# MainControl.net
KiCad netlist of a schematic drawn in EAGLE
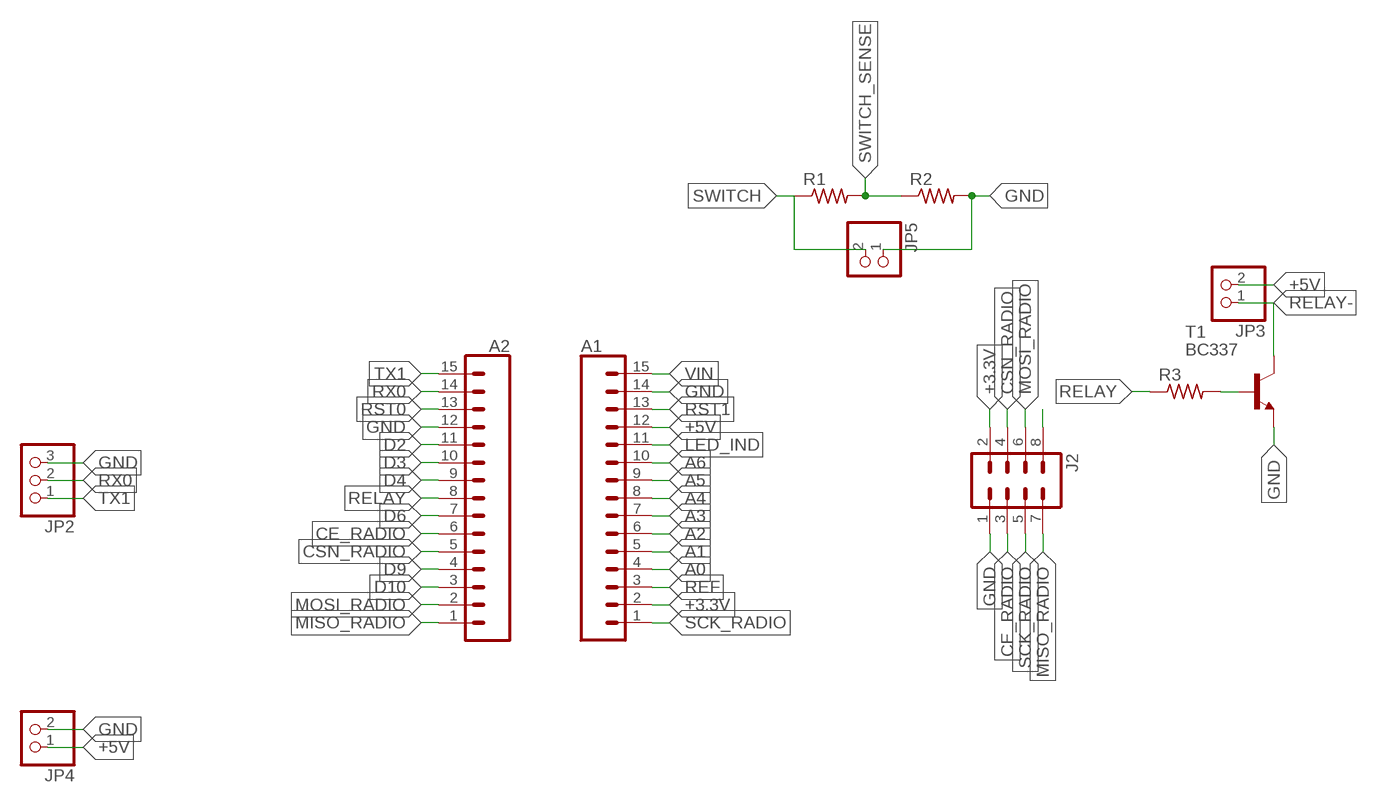
[diagram p0: schematic, sheet 1]

(export (version "E")
  (design (tool "Eeschema 10.0.6"))
  (components
    (comp (ref "A1")
      (value "CONN_15")
      (footprint "eagle-import:1X15")
      (fields (field (name "SPICEPREFIX") "X"))
      (libsource (lib "eagle-import") (part "CONN_15"))
    )
    (comp (ref "A2")
      (value "CONN_15")
      (footprint "eagle-import:1X15")
      (libsource (lib "eagle-import") (part "CONN_15"))
    )
    (comp (ref "J2")
      (value "MA04-2")
      (footprint "eagle-import:MA04-2")
      (libsource (lib "eagle-import") (part "MA04-2"))
    )
    (comp (ref "JP2")
      (value "PINHD-1X3")
      (footprint "eagle-import:1X03")
      (libsource (lib "eagle-import") (part "PINHD-1X3"))
    )
    (comp (ref "JP3")
      (value "PINHD-1X2")
      (footprint "eagle-import:1X02")
      (libsource (lib "eagle-import") (part "PINHD-1X2"))
    )
    (comp (ref "JP4")
      (value "PINHD-1X2")
      (footprint "eagle-import:1X02")
      (libsource (lib "eagle-import") (part "PINHD-1X2"))
    )
    (comp (ref "JP5")
      (value "PINHD-1X2")
      (footprint "eagle-import:1X02")
      (libsource (lib "eagle-import") (part "PINHD-1X2"))
    )
    (comp (ref "R1")
      (value "R-US_0204/7")
      (footprint "eagle-import:0204_7")
      (libsource (lib "eagle-import") (part "R-US_0204/7"))
    )
    (comp (ref "R2")
      (value "R-US_0204/7")
      (footprint "eagle-import:0204_7")
      (libsource (lib "eagle-import") (part "R-US_0204/7"))
    )
    (comp (ref "R3")
      (value "R-US_0204/7")
      (footprint "eagle-import:0204_7")
      (libsource (lib "eagle-import") (part "R-US_0204/7"))
    )
    (comp (ref "T1")
      (value "BC337")
      (footprint "eagle-import:TO92")
      (libsource (lib "eagle-import") (part "BC337"))
    )
  )
  (nets
    (net (code "1") (name "+3.3V") (class "Default")
      (node (ref "A1") (pin "2") (pinfunction "2_2") (pintype "passive"))
      (node (ref "J2") (pin "2") (pinfunction "2_2") (pintype "passive"))
    )
    (net (code "2") (name "+5V") (class "Default")
      (node (ref "A1") (pin "12") (pinfunction "12_12") (pintype "passive"))
      (node (ref "JP3") (pin "2") (pinfunction "2_2") (pintype "passive"))
      (node (ref "JP4") (pin "1") (pinfunction "1_1") (pintype "passive"))
    )
    (net (code "3") (name "A0") (class "Default")
      (node (ref "A1") (pin "4") (pinfunction "4_4") (pintype "passive"))
    )
    (net (code "4") (name "A1") (class "Default")
      (node (ref "A1") (pin "5") (pinfunction "5_5") (pintype "passive"))
    )
    (net (code "5") (name "A2") (class "Default")
      (node (ref "A1") (pin "6") (pinfunction "6_6") (pintype "passive"))
    )
    (net (code "6") (name "A3") (class "Default")
      (node (ref "A1") (pin "7") (pinfunction "7_7") (pintype "passive"))
    )
    (net (code "7") (name "A4") (class "Default")
      (node (ref "A1") (pin "8") (pinfunction "8_8") (pintype "passive"))
    )
    (net (code "8") (name "A5") (class "Default")
      (node (ref "A1") (pin "9") (pinfunction "9_9") (pintype "passive"))
    )
    (net (code "9") (name "A6") (class "Default")
      (node (ref "A1") (pin "10") (pinfunction "10_10") (pintype "passive"))
    )
    (net (code "10") (name "CE_RADIO") (class "Default")
      (node (ref "A2") (pin "6") (pinfunction "6_6") (pintype "passive"))
      (node (ref "J2") (pin "3") (pinfunction "3_3") (pintype "passive"))
    )
    (net (code "11") (name "CSN_RADIO") (class "Default")
      (node (ref "A2") (pin "5") (pinfunction "5_5") (pintype "passive"))
      (node (ref "J2") (pin "4") (pinfunction "4_4") (pintype "passive"))
    )
    (net (code "12") (name "D2") (class "Default")
      (node (ref "A2") (pin "11") (pinfunction "11_11") (pintype "passive"))
    )
    (net (code "13") (name "D3") (class "Default")
      (node (ref "A2") (pin "10") (pinfunction "10_10") (pintype "passive"))
    )
    (net (code "14") (name "D4") (class "Default")
      (node (ref "A2") (pin "9") (pinfunction "9_9") (pintype "passive"))
    )
    (net (code "15") (name "D6") (class "Default")
      (node (ref "A2") (pin "7") (pinfunction "7_7") (pintype "passive"))
    )
    (net (code "16") (name "D9") (class "Default")
      (node (ref "A2") (pin "4") (pinfunction "4_4") (pintype "passive"))
    )
    (net (code "17") (name "D10") (class "Default")
      (node (ref "A2") (pin "3") (pinfunction "3_3") (pintype "passive"))
    )
    (net (code "18") (name "GND") (class "Default")
      (node (ref "A1") (pin "14") (pinfunction "14_14") (pintype "passive"))
      (node (ref "A2") (pin "12") (pinfunction "12_12") (pintype "passive"))
      (node (ref "J2") (pin "1") (pinfunction "1_1") (pintype "passive"))
      (node (ref "JP2") (pin "3") (pinfunction "3_3") (pintype "passive"))
      (node (ref "JP4") (pin "2") (pinfunction "2_2") (pintype "passive"))
      (node (ref "JP5") (pin "1") (pinfunction "1_1") (pintype "passive"))
      (node (ref "R2") (pin "2") (pinfunction "2_2") (pintype "passive"))
      (node (ref "T1") (pin "1") (pinfunction "E_1") (pintype "passive"))
    )
    (net (code "19") (name "LED_IND") (class "Default")
      (node (ref "A1") (pin "11") (pinfunction "11_11") (pintype "passive"))
    )
    (net (code "20") (name "MISO_RADIO") (class "Default")
      (node (ref "A2") (pin "1") (pinfunction "1_1") (pintype "passive"))
      (node (ref "J2") (pin "7") (pinfunction "7_7") (pintype "passive"))
    )
    (net (code "21") (name "MOSI_RADIO") (class "Default")
      (node (ref "A2") (pin "2") (pinfunction "2_2") (pintype "passive"))
      (node (ref "J2") (pin "6") (pinfunction "6_6") (pintype "passive"))
    )
    (net (code "22") (name "Net-(T1-B)") (class "Default")
      (node (ref "R3") (pin "2") (pinfunction "2_2") (pintype "passive"))
      (node (ref "T1") (pin "2") (pinfunction "B_2") (pintype "passive"))
    )
    (net (code "23") (name "REF") (class "Default")
      (node (ref "A1") (pin "3") (pinfunction "3_3") (pintype "passive"))
    )
    (net (code "24") (name "RELAY") (class "Default")
      (node (ref "A2") (pin "8") (pinfunction "8_8") (pintype "passive"))
      (node (ref "R3") (pin "1") (pinfunction "1_1") (pintype "passive"))
    )
    (net (code "25") (name "RELAY-") (class "Default")
      (node (ref "JP3") (pin "1") (pinfunction "1_1") (pintype "passive"))
      (node (ref "T1") (pin "3") (pinfunction "C_3") (pintype "passive"))
    )
    (net (code "26") (name "RST0") (class "Default")
      (node (ref "A2") (pin "13") (pinfunction "13_13") (pintype "passive"))
    )
    (net (code "27") (name "RST1") (class "Default")
      (node (ref "A1") (pin "13") (pinfunction "13_13") (pintype "passive"))
    )
    (net (code "28") (name "RX0") (class "Default")
      (node (ref "A2") (pin "14") (pinfunction "14_14") (pintype "passive"))
      (node (ref "JP2") (pin "2") (pinfunction "2_2") (pintype "passive"))
    )
    (net (code "29") (name "SCK_RADIO") (class "Default")
      (node (ref "A1") (pin "1") (pinfunction "1_1") (pintype "passive"))
      (node (ref "J2") (pin "5") (pinfunction "5_5") (pintype "passive"))
    )
    (net (code "30") (name "SWITCH") (class "Default")
      (node (ref "JP5") (pin "2") (pinfunction "2_2") (pintype "passive"))
      (node (ref "R1") (pin "1") (pinfunction "1_1") (pintype "passive"))
    )
    (net (code "31") (name "SWITCH_SENSE") (class "Default")
      (node (ref "R1") (pin "2") (pinfunction "2_2") (pintype "passive"))
      (node (ref "R2") (pin "1") (pinfunction "1_1") (pintype "passive"))
    )
    (net (code "32") (name "TX1") (class "Default")
      (node (ref "A2") (pin "15") (pinfunction "15_15") (pintype "passive"))
      (node (ref "JP2") (pin "1") (pinfunction "1_1") (pintype "passive"))
    )
    (net (code "33") (name "VIN") (class "Default")
      (node (ref "A1") (pin "15") (pinfunction "15_15") (pintype "passive"))
    )
    (net (code "34") (name "unconnected-(J2-Pad8)") (class "Default")
      (node (ref "J2") (pin "8") (pinfunction "8_8") (pintype "passive"))
    )
  )
)
